# Watchdog.net
KiCad netlist of a schematic drawn in Altium Designer
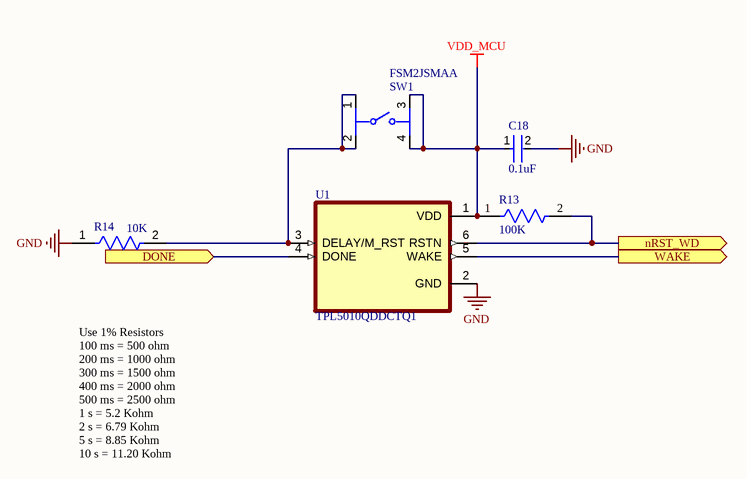
[diagram p0: Watchdog.SchDoc]

(export (version "E")
  (design (tool "Eeschema 10.0.6"))
  (components
    (comp (ref "C18")
      (value "0.1uF")
      (footprint "FP-C0603C-CF-MFG")
      (description "CAP CER 0.1UF 50V X7R 0603")
      (fields (field (name "TOLERANCE") "0.1") (field (name "MANUFACTURER") "KEMET"))
      (libsource (lib "Altium Content Vault") (part "b4654b650e69147ec39a6b967a45e02"))
    )
    (comp (ref "R13")
      (value "100K")
      (footprint "FP-ERA3A-MFG")
      (fields (field (name "TOLERANCE") "0.1%"))
      (libsource (lib "Altium Content Vault") (part "1029c3af85768c4190bb7ad29bc67b5"))
    )
    (comp (ref "R14")
      (value "10K")
      (footprint "FP-RK73B1J-MFG")
      (description "RES 10K OHM 5% 1/10W 0603")
      (fields (field (name "TOLERANCE") "5%"))
      (libsource (lib "Altium Content Vault") (part "1029c3af85768c4190bb7ad29bc67b5"))
    )
    (comp (ref "SW1")
      (value "FSM2JSMAA")
      (footprint "FP-FSM2JSMAA-MFG")
      (description "SWITCH TACTILE SPST-NO 0.05A 24V")
      (fields
        (field (name "MANUFACTURER") "TE Connectivity")
        (field (name "OCTOPART") "https://octopart.com/fsm2jsmaa-te+connectivity-41720620")
      )
      (libsource (lib "Altium Content Vault") (part "b8895f3f4cefb76e1819d2863dba89b"))
    )
    (comp (ref "U1")
      (value "TPL5010QDDCTQ1")
      (footprint "SOT95P280X110-6N")
      (description "Automotive AEC-Q100, nano-powered system timer with watchdog function")
      (fields (field (name "MF") "Texas Instruments"))
      (libsource (lib "Hitesh Bhoyar") (part "TPL5010QDDCTQ1"))
    )
  )
  (nets
    (net (code "1") (name "/DONE") (class "Default")
      (node (ref "U1") (pin "4") (pinfunction "DONE_4") (pintype "input"))
    )
    (net (code "2") (name "/WAKE") (class "Default")
      (node (ref "U1") (pin "5") (pinfunction "WAKE_5") (pintype "output"))
    )
    (net (code "3") (name "/nRST_WD") (class "Default")
      (node (ref "R13") (pin "2") (pinfunction "2_2") (pintype "passive"))
      (node (ref "U1") (pin "6") (pinfunction "RSTN_6") (pintype "output"))
    )
    (net (code "4") (name "GND") (class "Default")
      (node (ref "C18") (pin "2") (pinfunction "2_2") (pintype "passive"))
      (node (ref "R14") (pin "1") (pinfunction "1_1") (pintype "passive"))
      (node (ref "U1") (pin "2") (pinfunction "GND_2") (pintype "power_in"))
    )
    (net (code "5") (name "Net-(U1-DELAY{slash}M_RST)") (class "Default")
      (node (ref "R14") (pin "2") (pinfunction "2_2") (pintype "passive"))
      (node (ref "SW1") (pin "1") (pinfunction "1_1") (pintype "passive"))
      (node (ref "SW1") (pin "2") (pinfunction "2_2") (pintype "passive"))
      (node (ref "U1") (pin "3") (pinfunction "DELAY/M_RST_3") (pintype "input"))
    )
    (net (code "6") (name "VDD_MCU") (class "Default")
      (node (ref "C18") (pin "1") (pinfunction "1_1") (pintype "passive"))
      (node (ref "R13") (pin "1") (pinfunction "1_1") (pintype "passive"))
      (node (ref "SW1") (pin "3") (pinfunction "3_3") (pintype "passive"))
      (node (ref "SW1") (pin "4") (pinfunction "4_4") (pintype "passive"))
      (node (ref "U1") (pin "1") (pinfunction "VDD_1") (pintype "power_in"))
    )
  )
)
